# outputRelay.net
KiCad netlist of a schematic drawn in Altium Designer
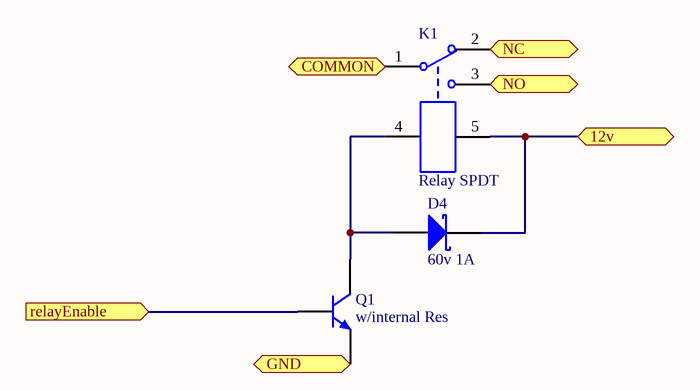
[diagram p0: outputRelay.SchDoc]

(export (version "E")
  (design (tool "Eeschema 10.0.6"))
  (components
    (comp (ref "D4")
      (value "60v 1A")
      (footprint "SOD323")
      (fields
        (field (name "PART NUMBER") "PMEG6010CEJ")
        (field (name "VOLTAGE") "60V")
        (field (name "AUTHOR") "Willem Pietersz")
      )
      (libsource (lib "OurDb") (part "SCHOTTKY"))
    )
    (comp (ref "K1")
      (value "Relay SPDT")
      (footprint "RELAY-G5LA-1")
      (description "Relay, Single-Pole Dual-Throw Relay")
      (fields
        (field (name "PART NUMBER") "G5LA-14")
        (field (name "VOLTAGE") "12")
        (field (name "PUBLISHER") "Altium Limited")
        (field (name "AUTHOR") "Willem Pietersz")
      )
      (libsource (lib "OurDb") (part "Relay-SPDT"))
    )
    (comp (ref "Q1")
      (value "w/internal Res")
      (footprint "SOT-323-NPN")
      (description "Transistor")
      (fields (field (name "PART NUMBER") "PDTC124TU") (field (name "VOLTAGE") "50"))
      (libsource (lib "OurDb") (part "NPN"))
    )
  )
  (nets
    (net (code "1") (name "/12v") (class "Default")
      (node (ref "D4") (pin "2") (pinfunction "2_2") (pintype "passive"))
      (node (ref "K1") (pin "5") (pinfunction "5_5") (pintype "passive"))
    )
    (net (code "2") (name "/COMMON") (class "Default")
      (node (ref "K1") (pin "1") (pinfunction "1_1") (pintype "passive"))
    )
    (net (code "3") (name "/GND") (class "Default")
      (node (ref "Q1") (pin "E") (pinfunction "E_E") (pintype "passive"))
    )
    (net (code "4") (name "/NC") (class "Default")
      (node (ref "K1") (pin "2") (pinfunction "2_2") (pintype "passive"))
    )
    (net (code "5") (name "/NO") (class "Default")
      (node (ref "K1") (pin "3") (pinfunction "3_3") (pintype "passive"))
    )
    (net (code "6") (name "/relayEnable") (class "Default")
      (node (ref "Q1") (pin "B") (pinfunction "B_B") (pintype "passive"))
    )
    (net (code "7") (name "Net-(D4-Pad1)") (class "Default")
      (node (ref "D4") (pin "1") (pinfunction "1_1") (pintype "passive"))
      (node (ref "K1") (pin "4") (pinfunction "4_4") (pintype "passive"))
      (node (ref "Q1") (pin "C") (pinfunction "C_C") (pintype "passive"))
    )
  )
)
